# atmegademo.net
KiCad netlist of a schematic drawn in EAGLE
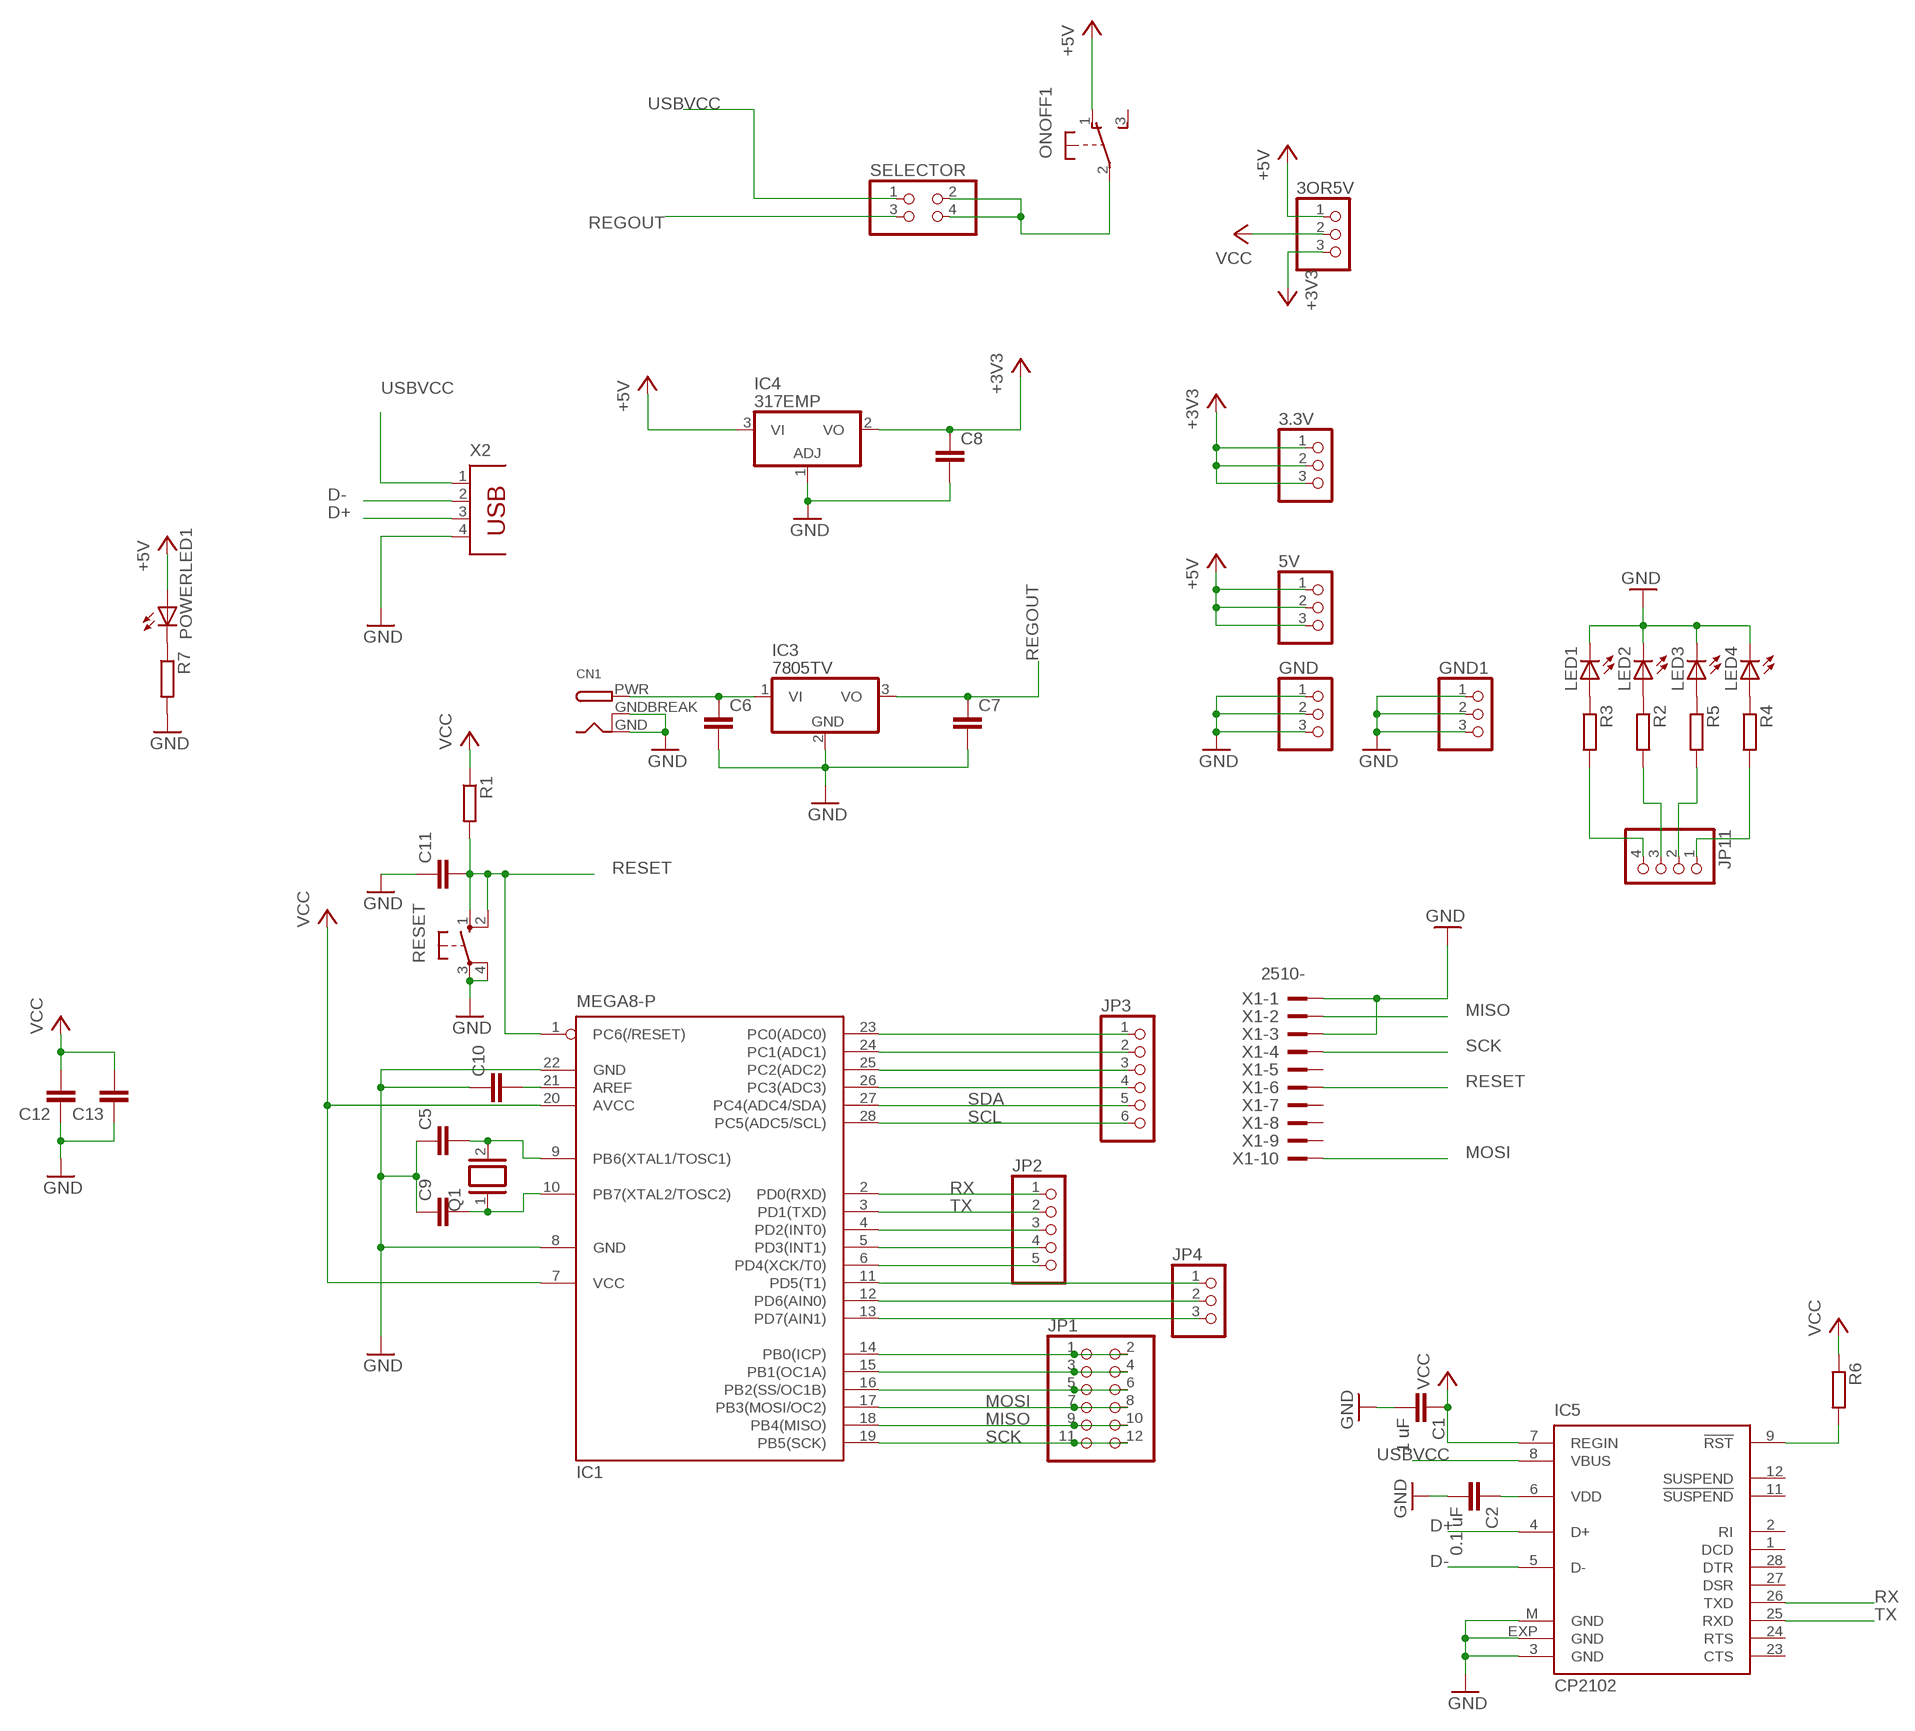
[diagram p0: schematic, sheet 1]

(export (version "E")
  (design (tool "Eeschema 10.0.6"))
  (components
    (comp (ref "3.3V")
      (value "PINHD-1X3")
      (footprint "eagle-import:1X03")
      (libsource (lib "eagle-import") (part "PINHD-1X3"))
    )
    (comp (ref "3OR5V")
      (value "PINHD-1X3")
      (footprint "eagle-import:1X03")
      (libsource (lib "eagle-import") (part "PINHD-1X3"))
    )
    (comp (ref "5V")
      (value "PINHD-1X3")
      (footprint "eagle-import:1X03")
      (libsource (lib "eagle-import") (part "PINHD-1X3"))
    )
    (comp (ref "C1")
      (value "1 uF")
      (footprint "eagle-import:C0805K")
      (libsource (lib "eagle-import") (part "C-EUC0805K"))
    )
    (comp (ref "C2")
      (value "0.1 uF")
      (footprint "eagle-import:C0805K")
      (libsource (lib "eagle-import") (part "C-EUC0805K"))
    )
    (comp (ref "C5")
      (value "C-EUC0805K")
      (footprint "eagle-import:C0805K")
      (libsource (lib "eagle-import") (part "C-EUC0805K"))
    )
    (comp (ref "C6")
      (value "C-EUC0805K")
      (footprint "eagle-import:C0805K")
      (libsource (lib "eagle-import") (part "C-EUC0805K"))
    )
    (comp (ref "C7")
      (value "C-EUC0805K")
      (footprint "eagle-import:C0805K")
      (libsource (lib "eagle-import") (part "C-EUC0805K"))
    )
    (comp (ref "C8")
      (value "C-EUC0805K")
      (footprint "eagle-import:C0805K")
      (libsource (lib "eagle-import") (part "C-EUC0805K"))
    )
    (comp (ref "C9")
      (value "C-EUC0805K")
      (footprint "eagle-import:C0805K")
      (libsource (lib "eagle-import") (part "C-EUC0805K"))
    )
    (comp (ref "C10")
      (value "C-EUC0805K")
      (footprint "eagle-import:C0805K")
      (libsource (lib "eagle-import") (part "C-EUC0805K"))
    )
    (comp (ref "C11")
      (value "C-EUC0805K")
      (footprint "eagle-import:C0805K")
      (libsource (lib "eagle-import") (part "C-EUC0805K"))
    )
    (comp (ref "C12")
      (value "C-EUC0805K")
      (footprint "eagle-import:C0805K")
      (libsource (lib "eagle-import") (part "C-EUC0805K"))
    )
    (comp (ref "C13")
      (value "C-EUC0805K")
      (footprint "eagle-import:C0805K")
      (libsource (lib "eagle-import") (part "C-EUC0805K"))
    )
    (comp (ref "CN1")
      (value "DCBARRELPTH")
      (footprint "eagle-import:DCJACK_2MM_PTH")
      (libsource (lib "eagle-import") (part "DCBARRELPTH"))
    )
    (comp (ref "GND")
      (value "PINHD-1X3")
      (footprint "eagle-import:1X03")
      (libsource (lib "eagle-import") (part "PINHD-1X3"))
    )
    (comp (ref "GND1")
      (value "PINHD-1X3")
      (footprint "eagle-import:1X03")
      (libsource (lib "eagle-import") (part "PINHD-1X3"))
    )
    (comp (ref "IC1")
      (value "MEGA8-P")
      (footprint "eagle-import:DIL28-3")
      (libsource (lib "eagle-import") (part "MEGA8-P"))
    )
    (comp (ref "IC3")
      (value "7805TV")
      (footprint "eagle-import:TO220V")
      (libsource (lib "eagle-import") (part "78TV05"))
    )
    (comp (ref "IC4")
      (value "317EMP")
      (footprint "eagle-import:SOT223")
      (libsource (lib "eagle-import") (part "317EMP"))
    )
    (comp (ref "IC5")
      (value "CP2102")
      (footprint "eagle-import:MLP28")
      (fields (field (name "MF") "FARNELL") (field (name "MPN") "CP2102-GM"))
      (libsource (lib "eagle-import") (part "CP2102"))
    )
    (comp (ref "JP1")
      (value "PINHD-2X6")
      (footprint "eagle-import:2X06")
      (libsource (lib "eagle-import") (part "PINHD-2X6"))
    )
    (comp (ref "JP2")
      (value "PINHD-1X5")
      (footprint "eagle-import:1X05")
      (libsource (lib "eagle-import") (part "PINHD-1X5"))
    )
    (comp (ref "JP3")
      (value "PINHD-1X6")
      (footprint "eagle-import:1X06")
      (libsource (lib "eagle-import") (part "PINHD-1X6"))
    )
    (comp (ref "JP4")
      (value "PINHD-1X3")
      (footprint "eagle-import:1X03")
      (libsource (lib "eagle-import") (part "pinhead_PINHD-1X3"))
    )
    (comp (ref "JP11")
      (value "PINHD-1X4")
      (footprint "eagle-import:1X04")
      (libsource (lib "eagle-import") (part "PINHD-1X4"))
    )
    (comp (ref "LED1")
      (value "LEDCHIP-LED0805")
      (footprint "eagle-import:CHIP-LED0805")
      (libsource (lib "eagle-import") (part "LEDCHIP-LED0805"))
    )
    (comp (ref "LED2")
      (value "LEDCHIP-LED0805")
      (footprint "eagle-import:CHIP-LED0805")
      (libsource (lib "eagle-import") (part "LEDCHIP-LED0805"))
    )
    (comp (ref "LED3")
      (value "LEDCHIP-LED0805")
      (footprint "eagle-import:CHIP-LED0805")
      (libsource (lib "eagle-import") (part "LEDCHIP-LED0805"))
    )
    (comp (ref "LED4")
      (value "LEDCHIP-LED0805")
      (footprint "eagle-import:CHIP-LED0805")
      (libsource (lib "eagle-import") (part "LEDCHIP-LED0805"))
    )
    (comp (ref "ONOFF")
      (value "EG1213")
      (footprint "eagle-import:EG1213")
      (libsource (lib "eagle-import") (part "EG1213"))
    )
    (comp (ref "POWERLED1")
      (value "LEDCHIP-LED0805")
      (footprint "eagle-import:CHIP-LED0805")
      (libsource (lib "eagle-import") (part "LEDCHIP-LED0805"))
    )
    (comp (ref "Q1")
      (value "XTAL/S")
      (footprint "eagle-import:QS")
      (libsource (lib "eagle-import") (part "XTAL/S"))
    )
    (comp (ref "R1")
      (value "R-EU_0207/12")
      (footprint "eagle-import:0207_12")
      (libsource (lib "eagle-import") (part "R-EU_0207/12"))
    )
    (comp (ref "R2")
      (value "R-EU_R0805")
      (footprint "eagle-import:R0805")
      (libsource (lib "eagle-import") (part "R-EU_R0805"))
    )
    (comp (ref "R3")
      (value "R-EU_R0805")
      (footprint "eagle-import:R0805")
      (libsource (lib "eagle-import") (part "R-EU_R0805"))
    )
    (comp (ref "R4")
      (value "R-EU_R0805")
      (footprint "eagle-import:R0805")
      (libsource (lib "eagle-import") (part "R-EU_R0805"))
    )
    (comp (ref "R5")
      (value "R-EU_R0805")
      (footprint "eagle-import:R0805")
      (libsource (lib "eagle-import") (part "R-EU_R0805"))
    )
    (comp (ref "R6")
      (value "R-EU_R0805")
      (footprint "eagle-import:R0805")
      (libsource (lib "eagle-import") (part "R-EU_R0805"))
    )
    (comp (ref "R7")
      (value "R-EU_R0805")
      (footprint "eagle-import:R0805")
      (libsource (lib "eagle-import") (part "R-EU_R0805"))
    )
    (comp (ref "RESET")
      (value "10-XX")
      (footprint "eagle-import:B3F-10XX")
      (fields (field (name "MPN") "B3F-1000"))
      (libsource (lib "eagle-import") (part "10-XX"))
    )
    (comp (ref "SELECTOR")
      (value "PINHD-2X2")
      (footprint "eagle-import:2X02")
      (libsource (lib "eagle-import") (part "PINHD-2X2"))
    )
    (comp (ref "X1")
      (value "2510-")
      (footprint "eagle-import:PAK100_2500-10")
      (fields (field (name "MF") "3M") (field (name "MPN") "2510-6002UB"))
      (libsource (lib "eagle-import") (part "2510-"))
    )
    (comp (ref "X2")
      (value "PN61729")
      (footprint "eagle-import:PN61729")
      (libsource (lib "eagle-import") (part "PN61729"))
    )
  )
  (nets
    (net (code "1") (name "+3V3") (class "Default")
      (node (ref "3.3V") (pin "1") (pinfunction "1_1") (pintype "passive"))
      (node (ref "3.3V") (pin "2") (pinfunction "2_2") (pintype "passive"))
      (node (ref "3.3V") (pin "3") (pinfunction "3_3") (pintype "passive"))
      (node (ref "3OR5V") (pin "3") (pinfunction "3_3") (pintype "passive"))
      (node (ref "C8") (pin "1") (pinfunction "1_1") (pintype "passive"))
      (node (ref "IC4") (pin "2") (pinfunction "VO_2") (pintype "passive"))
    )
    (net (code "2") (name "+5V") (class "Default")
      (node (ref "3OR5V") (pin "1") (pinfunction "1_1") (pintype "passive"))
      (node (ref "5V") (pin "1") (pinfunction "1_1") (pintype "passive"))
      (node (ref "5V") (pin "2") (pinfunction "2_2") (pintype "passive"))
      (node (ref "5V") (pin "3") (pinfunction "3_3") (pintype "passive"))
      (node (ref "IC4") (pin "3") (pinfunction "VI_3") (pintype "input"))
      (node (ref "ONOFF") (pin "1") (pinfunction "O_1") (pintype "passive"))
      (node (ref "POWERLED1") (pin "A") (pinfunction "A_A") (pintype "passive"))
    )
    (net (code "3") (name "/D+") (class "Default")
      (node (ref "IC5") (pin "4") (pinfunction "D+_4") (pintype "bidirectional"))
      (node (ref "X2") (pin "3") (pinfunction "3_3") (pintype "passive"))
    )
    (net (code "4") (name "/D-") (class "Default")
      (node (ref "IC5") (pin "5") (pinfunction "D-_5") (pintype "bidirectional"))
      (node (ref "X2") (pin "2") (pinfunction "2_2") (pintype "passive"))
    )
    (net (code "5") (name "/MISO") (class "Default")
      (node (ref "IC1") (pin "18") (pinfunction "PB4(MISO)_18") (pintype "bidirectional"))
      (node (ref "JP1") (pin "10") (pinfunction "10_10") (pintype "passive"))
      (node (ref "JP1") (pin "9") (pinfunction "9_9") (pintype "passive"))
      (node (ref "X1") (pin "2") (pinfunction "KL_2") (pintype "passive"))
    )
    (net (code "6") (name "/MOSI") (class "Default")
      (node (ref "IC1") (pin "17") (pinfunction "PB3(MOSI/OC2)_17") (pintype "bidirectional"))
      (node (ref "JP1") (pin "7") (pinfunction "7_7") (pintype "passive"))
      (node (ref "JP1") (pin "8") (pinfunction "8_8") (pintype "passive"))
      (node (ref "X1") (pin "10") (pinfunction "KL_10") (pintype "passive"))
    )
    (net (code "7") (name "/REGOUT") (class "Default")
      (node (ref "C7") (pin "1") (pinfunction "1_1") (pintype "passive"))
      (node (ref "IC3") (pin "3") (pinfunction "VO_3") (pintype "passive"))
      (node (ref "SELECTOR") (pin "3") (pinfunction "3_3") (pintype "passive"))
    )
    (net (code "8") (name "/RESET") (class "Default")
      (node (ref "C11") (pin "2") (pinfunction "2_2") (pintype "passive"))
      (node (ref "IC1") (pin "1") (pinfunction "PC6(/RESET)_1") (pintype "bidirectional"))
      (node (ref "R1") (pin "2") (pinfunction "2_2") (pintype "passive"))
      (node (ref "RESET") (pin "1") (pinfunction "S_1") (pintype "passive"))
      (node (ref "RESET") (pin "2") (pinfunction "S1_2") (pintype "passive"))
      (node (ref "X1") (pin "6") (pinfunction "KL_6") (pintype "passive"))
    )
    (net (code "9") (name "/RX") (class "Default")
      (node (ref "IC1") (pin "2") (pinfunction "PD0(RXD)_2") (pintype "bidirectional"))
      (node (ref "IC5") (pin "26") (pinfunction "TXD_26") (pintype "output"))
      (node (ref "JP2") (pin "1") (pinfunction "1_1") (pintype "passive"))
    )
    (net (code "10") (name "/SCK") (class "Default")
      (node (ref "IC1") (pin "19") (pinfunction "PB5(SCK)_19") (pintype "bidirectional"))
      (node (ref "JP1") (pin "11") (pinfunction "11_11") (pintype "passive"))
      (node (ref "JP1") (pin "12") (pinfunction "12_12") (pintype "passive"))
      (node (ref "X1") (pin "4") (pinfunction "KL_4") (pintype "passive"))
    )
    (net (code "11") (name "/SCL") (class "Default")
      (node (ref "IC1") (pin "28") (pinfunction "PC5(ADC5/SCL)_28") (pintype "bidirectional"))
      (node (ref "JP3") (pin "6") (pinfunction "6_6") (pintype "passive"))
    )
    (net (code "12") (name "/SDA") (class "Default")
      (node (ref "IC1") (pin "27") (pinfunction "PC4(ADC4/SDA)_27") (pintype "bidirectional"))
      (node (ref "JP3") (pin "5") (pinfunction "5_5") (pintype "passive"))
    )
    (net (code "13") (name "/TX") (class "Default")
      (node (ref "IC1") (pin "3") (pinfunction "PD1(TXD)_3") (pintype "bidirectional"))
      (node (ref "IC5") (pin "25") (pinfunction "RXD_25") (pintype "input"))
      (node (ref "JP2") (pin "2") (pinfunction "2_2") (pintype "passive"))
    )
    (net (code "14") (name "/USBVCC") (class "Default")
      (node (ref "IC5") (pin "8") (pinfunction "VBUS_8") (pintype "input"))
      (node (ref "SELECTOR") (pin "1") (pinfunction "1_1") (pintype "passive"))
      (node (ref "X2") (pin "1") (pinfunction "1_1") (pintype "passive"))
    )
    (net (code "15") (name "GND") (class "Default")
      (node (ref "C1") (pin "2") (pinfunction "2_2") (pintype "passive"))
      (node (ref "C10") (pin "1") (pinfunction "1_1") (pintype "passive"))
      (node (ref "C11") (pin "1") (pinfunction "1_1") (pintype "passive"))
      (node (ref "C12") (pin "1") (pinfunction "1_1") (pintype "passive"))
      (node (ref "C13") (pin "1") (pinfunction "1_1") (pintype "passive"))
      (node (ref "C2") (pin "2") (pinfunction "2_2") (pintype "passive"))
      (node (ref "C5") (pin "1") (pinfunction "1_1") (pintype "passive"))
      (node (ref "C6") (pin "2") (pinfunction "2_2") (pintype "passive"))
      (node (ref "C7") (pin "2") (pinfunction "2_2") (pintype "passive"))
      (node (ref "C8") (pin "2") (pinfunction "2_2") (pintype "passive"))
      (node (ref "C9") (pin "1") (pinfunction "1_1") (pintype "passive"))
      (node (ref "CN1") (pin "GND") (pinfunction "GND_GND") (pintype "power_in"))
      (node (ref "CN1") (pin "GNDBREAK") (pinfunction "GNDBREAK_GNDBREAK") (pintype "power_in"))
      (node (ref "GND") (pin "1") (pinfunction "1_1") (pintype "passive"))
      (node (ref "GND") (pin "2") (pinfunction "2_2") (pintype "passive"))
      (node (ref "GND") (pin "3") (pinfunction "3_3") (pintype "passive"))
      (node (ref "GND1") (pin "1") (pinfunction "1_1") (pintype "passive"))
      (node (ref "GND1") (pin "2") (pinfunction "2_2") (pintype "passive"))
      (node (ref "GND1") (pin "3") (pinfunction "3_3") (pintype "passive"))
      (node (ref "IC1") (pin "22") (pinfunction "GND_22") (pintype "power_in"))
      (node (ref "IC1") (pin "8") (pinfunction "GND_8") (pintype "power_in"))
      (node (ref "IC3") (pin "2") (pinfunction "GND_2") (pintype "passive"))
      (node (ref "IC4") (pin "1") (pinfunction "ADJ_1") (pintype "input"))
      (node (ref "IC5") (pin "3") (pinfunction "GND_3") (pintype "power_in"))
      (node (ref "IC5") (pin "EXP") (pinfunction "GND_EXP") (pintype "power_in"))
      (node (ref "IC5") (pin "M") (pinfunction "GND_M") (pintype "power_in"))
      (node (ref "LED1") (pin "C") (pinfunction "C_C") (pintype "passive"))
      (node (ref "LED2") (pin "C") (pinfunction "C_C") (pintype "passive"))
      (node (ref "LED3") (pin "C") (pinfunction "C_C") (pintype "passive"))
      (node (ref "LED4") (pin "C") (pinfunction "C_C") (pintype "passive"))
      (node (ref "R7") (pin "2") (pinfunction "2_2") (pintype "passive"))
      (node (ref "RESET") (pin "3") (pinfunction "P_3") (pintype "passive"))
      (node (ref "RESET") (pin "4") (pinfunction "P1_4") (pintype "passive"))
      (node (ref "X1") (pin "1") (pinfunction "KL_1") (pintype "passive"))
      (node (ref "X1") (pin "3") (pinfunction "KL_3") (pintype "passive"))
      (node (ref "X2") (pin "4") (pinfunction "4_4") (pintype "passive"))
    )
    (net (code "16") (name "Net-(IC1-AREF)") (class "Default")
      (node (ref "C10") (pin "2") (pinfunction "2_2") (pintype "passive"))
      (node (ref "IC1") (pin "21") (pinfunction "AREF_21") (pintype "passive"))
    )
    (net (code "17") (name "Net-(IC1-PB0(ICP))") (class "Default")
      (node (ref "IC1") (pin "14") (pinfunction "PB0(ICP)_14") (pintype "bidirectional"))
      (node (ref "JP1") (pin "1") (pinfunction "1_1") (pintype "passive"))
      (node (ref "JP1") (pin "2") (pinfunction "2_2") (pintype "passive"))
    )
    (net (code "18") (name "Net-(IC1-PB1(OC1A))") (class "Default")
      (node (ref "IC1") (pin "15") (pinfunction "PB1(OC1A)_15") (pintype "bidirectional"))
      (node (ref "JP1") (pin "3") (pinfunction "3_3") (pintype "passive"))
      (node (ref "JP1") (pin "4") (pinfunction "4_4") (pintype "passive"))
    )
    (net (code "19") (name "Net-(IC1-PB2(SS{slash}OC1B))") (class "Default")
      (node (ref "IC1") (pin "16") (pinfunction "PB2(SS/OC1B)_16") (pintype "bidirectional"))
      (node (ref "JP1") (pin "5") (pinfunction "5_5") (pintype "passive"))
      (node (ref "JP1") (pin "6") (pinfunction "6_6") (pintype "passive"))
    )
    (net (code "20") (name "Net-(IC1-PB6(XTAL1{slash}TOSC1))") (class "Default")
      (node (ref "C5") (pin "2") (pinfunction "2_2") (pintype "passive"))
      (node (ref "IC1") (pin "9") (pinfunction "PB6(XTAL1/TOSC1)_9") (pintype "bidirectional"))
      (node (ref "Q1") (pin "2") (pinfunction "2_2") (pintype "passive"))
    )
    (net (code "21") (name "Net-(IC1-PB7(XTAL2{slash}TOSC2))") (class "Default")
      (node (ref "C9") (pin "2") (pinfunction "2_2") (pintype "passive"))
      (node (ref "IC1") (pin "10") (pinfunction "PB7(XTAL2/TOSC2)_10") (pintype "bidirectional"))
      (node (ref "Q1") (pin "1") (pinfunction "1_1") (pintype "passive"))
    )
    (net (code "22") (name "Net-(IC1-PC0(ADC0))") (class "Default")
      (node (ref "IC1") (pin "23") (pinfunction "PC0(ADC0)_23") (pintype "bidirectional"))
      (node (ref "JP3") (pin "1") (pinfunction "1_1") (pintype "passive"))
    )
    (net (code "23") (name "Net-(IC1-PC1(ADC1))") (class "Default")
      (node (ref "IC1") (pin "24") (pinfunction "PC1(ADC1)_24") (pintype "bidirectional"))
      (node (ref "JP3") (pin "2") (pinfunction "2_2") (pintype "passive"))
    )
    (net (code "24") (name "Net-(IC1-PC2(ADC2))") (class "Default")
      (node (ref "IC1") (pin "25") (pinfunction "PC2(ADC2)_25") (pintype "bidirectional"))
      (node (ref "JP3") (pin "3") (pinfunction "3_3") (pintype "passive"))
    )
    (net (code "25") (name "Net-(IC1-PC3(ADC3))") (class "Default")
      (node (ref "IC1") (pin "26") (pinfunction "PC3(ADC3)_26") (pintype "bidirectional"))
      (node (ref "JP3") (pin "4") (pinfunction "4_4") (pintype "passive"))
    )
    (net (code "26") (name "Net-(IC1-PD2(INT0))") (class "Default")
      (node (ref "IC1") (pin "4") (pinfunction "PD2(INT0)_4") (pintype "bidirectional"))
      (node (ref "JP2") (pin "3") (pinfunction "3_3") (pintype "passive"))
    )
    (net (code "27") (name "Net-(IC1-PD3(INT1))") (class "Default")
      (node (ref "IC1") (pin "5") (pinfunction "PD3(INT1)_5") (pintype "bidirectional"))
      (node (ref "JP2") (pin "4") (pinfunction "4_4") (pintype "passive"))
    )
    (net (code "28") (name "Net-(IC1-PD4(XCK{slash}T0))") (class "Default")
      (node (ref "IC1") (pin "6") (pinfunction "PD4(XCK/T0)_6") (pintype "bidirectional"))
      (node (ref "JP2") (pin "5") (pinfunction "5_5") (pintype "passive"))
    )
    (net (code "29") (name "Net-(IC1-PD5(T1))") (class "Default")
      (node (ref "IC1") (pin "11") (pinfunction "PD5(T1)_11") (pintype "bidirectional"))
      (node (ref "JP4") (pin "1") (pinfunction "1_1") (pintype "passive"))
    )
    (net (code "30") (name "Net-(IC1-PD6(AIN0))") (class "Default")
      (node (ref "IC1") (pin "12") (pinfunction "PD6(AIN0)_12") (pintype "bidirectional"))
      (node (ref "JP4") (pin "2") (pinfunction "2_2") (pintype "passive"))
    )
    (net (code "31") (name "Net-(IC1-PD7(AIN1))") (class "Default")
      (node (ref "IC1") (pin "13") (pinfunction "PD7(AIN1)_13") (pintype "bidirectional"))
      (node (ref "JP4") (pin "3") (pinfunction "3_3") (pintype "passive"))
    )
    (net (code "32") (name "Net-(IC3-VI)") (class "Default")
      (node (ref "C6") (pin "1") (pinfunction "1_1") (pintype "passive"))
      (node (ref "CN1") (pin "PWR") (pinfunction "PWR_PWR") (pintype "power_in"))
      (node (ref "IC3") (pin "1") (pinfunction "VI_1") (pintype "input"))
    )
    (net (code "33") (name "Net-(IC5-VDD)") (class "Default")
      (node (ref "C2") (pin "1") (pinfunction "1_1") (pintype "passive"))
      (node (ref "IC5") (pin "6") (pinfunction "VDD_6") (pintype "power_in"))
    )
    (net (code "34") (name "Net-(IC5-~{RST})") (class "Default")
      (node (ref "IC5") (pin "9") (pinfunction "~{RST}_9") (pintype "bidirectional"))
      (node (ref "R6") (pin "2") (pinfunction "2_2") (pintype "passive"))
    )
    (net (code "35") (name "Net-(JP11-Pad1)") (class "Default")
      (node (ref "JP11") (pin "1") (pinfunction "1_1") (pintype "passive"))
      (node (ref "R4") (pin "2") (pinfunction "2_2") (pintype "passive"))
    )
    (net (code "36") (name "Net-(JP11-Pad2)") (class "Default")
      (node (ref "JP11") (pin "2") (pinfunction "2_2") (pintype "passive"))
      (node (ref "R5") (pin "2") (pinfunction "2_2") (pintype "passive"))
    )
    (net (code "37") (name "Net-(JP11-Pad3)") (class "Default")
      (node (ref "JP11") (pin "3") (pinfunction "3_3") (pintype "passive"))
      (node (ref "R2") (pin "2") (pinfunction "2_2") (pintype "passive"))
    )
    (net (code "38") (name "Net-(JP11-Pad4)") (class "Default")
      (node (ref "JP11") (pin "4") (pinfunction "4_4") (pintype "passive"))
      (node (ref "R3") (pin "2") (pinfunction "2_2") (pintype "passive"))
    )
    (net (code "39") (name "Net-(LED1-PadA)") (class "Default")
      (node (ref "LED1") (pin "A") (pinfunction "A_A") (pintype "passive"))
      (node (ref "R3") (pin "1") (pinfunction "1_1") (pintype "passive"))
    )
    (net (code "40") (name "Net-(LED2-PadA)") (class "Default")
      (node (ref "LED2") (pin "A") (pinfunction "A_A") (pintype "passive"))
      (node (ref "R2") (pin "1") (pinfunction "1_1") (pintype "passive"))
    )
    (net (code "41") (name "Net-(LED3-PadA)") (class "Default")
      (node (ref "LED3") (pin "A") (pinfunction "A_A") (pintype "passive"))
      (node (ref "R5") (pin "1") (pinfunction "1_1") (pintype "passive"))
    )
    (net (code "42") (name "Net-(LED4-PadA)") (class "Default")
      (node (ref "LED4") (pin "A") (pinfunction "A_A") (pintype "passive"))
      (node (ref "R4") (pin "1") (pinfunction "1_1") (pintype "passive"))
    )
    (net (code "43") (name "Net-(ONOFFA-P)") (class "Default")
      (node (ref "ONOFF") (pin "2") (pinfunction "P_2") (pintype "passive"))
      (node (ref "SELECTOR") (pin "2") (pinfunction "2_2") (pintype "passive"))
      (node (ref "SELECTOR") (pin "4") (pinfunction "4_4") (pintype "passive"))
    )
    (net (code "44") (name "Net-(POWERLED1-PadC)") (class "Default")
      (node (ref "POWERLED1") (pin "C") (pinfunction "C_C") (pintype "passive"))
      (node (ref "R7") (pin "1") (pinfunction "1_1") (pintype "passive"))
    )
    (net (code "45") (name "VCC") (class "Default")
      (node (ref "3OR5V") (pin "2") (pinfunction "2_2") (pintype "passive"))
      (node (ref "C1") (pin "1") (pinfunction "1_1") (pintype "passive"))
      (node (ref "C12") (pin "2") (pinfunction "2_2") (pintype "passive"))
      (node (ref "C13") (pin "2") (pinfunction "2_2") (pintype "passive"))
      (node (ref "IC1") (pin "20") (pinfunction "AVCC_20") (pintype "power_in"))
      (node (ref "IC1") (pin "7") (pinfunction "VCC_7") (pintype "power_in"))
      (node (ref "IC5") (pin "7") (pinfunction "REGIN_7") (pintype "passive"))
      (node (ref "R1") (pin "1") (pinfunction "1_1") (pintype "passive"))
      (node (ref "R6") (pin "1") (pinfunction "1_1") (pintype "passive"))
    )
    (net (code "46") (name "unconnected-(IC5-CTS-Pad23)") (class "Default")
      (node (ref "IC5") (pin "23") (pinfunction "CTS_23") (pintype "input"))
    )
    (net (code "47") (name "unconnected-(IC5-DCD-Pad1)") (class "Default")
      (node (ref "IC5") (pin "1") (pinfunction "DCD_1") (pintype "input"))
    )
    (net (code "48") (name "unconnected-(IC5-DSR-Pad27)") (class "Default")
      (node (ref "IC5") (pin "27") (pinfunction "DSR_27") (pintype "input"))
    )
    (net (code "49") (name "unconnected-(IC5-DTR-Pad28)") (class "Default")
      (node (ref "IC5") (pin "28") (pinfunction "DTR_28") (pintype "output"))
    )
    (net (code "50") (name "unconnected-(IC5-RI-Pad2)") (class "Default")
      (node (ref "IC5") (pin "2") (pinfunction "RI_2") (pintype "input"))
    )
    (net (code "51") (name "unconnected-(IC5-RTS-Pad24)") (class "Default")
      (node (ref "IC5") (pin "24") (pinfunction "RTS_24") (pintype "output"))
    )
    (net (code "52") (name "unconnected-(IC5-SUSPEND-Pad12)") (class "Default")
      (node (ref "IC5") (pin "12") (pinfunction "SUSPEND_12") (pintype "output"))
    )
    (net (code "53") (name "unconnected-(IC5-~{SUSPEND}-Pad11)") (class "Default")
      (node (ref "IC5") (pin "11") (pinfunction "~{SUSPEND}_11") (pintype "output"))
    )
    (net (code "54") (name "unconnected-(ONOFFA-S-Pad3)") (class "Default")
      (node (ref "ONOFF") (pin "3") (pinfunction "S_3") (pintype "passive"))
    )
    (net (code "55") (name "unconnected-(X1F-KL-Pad5)") (class "Default")
      (node (ref "X1") (pin "5") (pinfunction "KL_5") (pintype "passive"))
    )
    (net (code "56") (name "unconnected-(X1H-KL-Pad7)") (class "Default")
      (node (ref "X1") (pin "7") (pinfunction "KL_7") (pintype "passive"))
    )
    (net (code "57") (name "unconnected-(X1I-KL-Pad8)") (class "Default")
      (node (ref "X1") (pin "8") (pinfunction "KL_8") (pintype "passive"))
    )
    (net (code "58") (name "unconnected-(X1J-KL-Pad9)") (class "Default")
      (node (ref "X1") (pin "9") (pinfunction "KL_9") (pintype "passive"))
    )
  )
)
